# MCU_144_POWER.net
KiCad netlist of a schematic drawn in Altium Designer
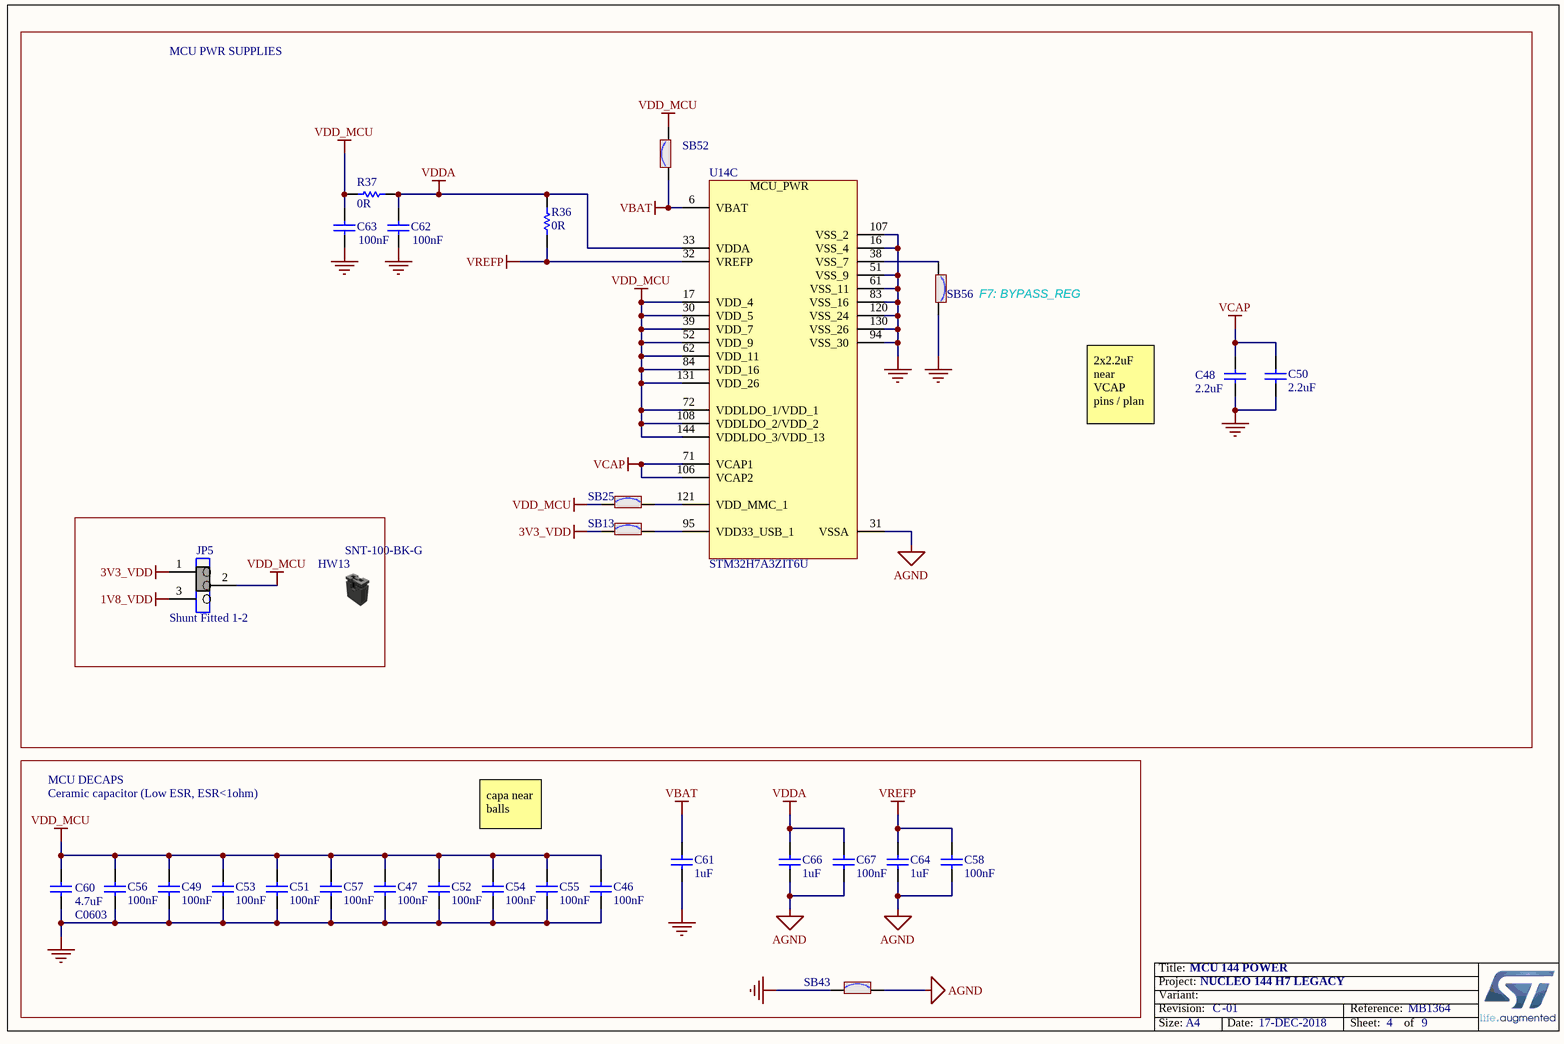
[diagram p0: MCU_144_POWER.SchDoc]

(export (version "E")
  (design (tool "Eeschema 10.0.6"))
  (components
    (comp (ref "C46")
      (value "100nF")
      (footprint "C0402")
      (description "[obsolete] Capacitor, MLCC,100nF, 10V, X7R, 10%, 0402, T=0.5mm")
      (fields
        (field (name "INTERNAL_PART_NUMBER") "MCD-01123")
        (field (name "MANUFACTURER_PART_NUMBER") "NRND_GRM155R71A104KA01")
        (field (name "PROVIDED_BY") "SUBCO")
      )
      (libsource (lib "MCD_PARTS_database") (part "Capacitor"))
    )
    (comp (ref "C47")
      (value "100nF")
      (footprint "C0402")
      (description "[obsolete] Capacitor, MLCC,100nF, 10V, X7R, 10%, 0402, T=0.5mm")
      (fields
        (field (name "INTERNAL_PART_NUMBER") "MCD-01123")
        (field (name "MANUFACTURER_PART_NUMBER") "NRND_GRM155R71A104KA01")
        (field (name "PROVIDED_BY") "SUBCO")
      )
      (libsource (lib "MCD_PARTS_database") (part "Capacitor"))
    )
    (comp (ref "C48")
      (value "2.2uF")
      (footprint "C0603")
      (description "Capacitor, MLCC, 2.2uF, 10V, X5R, 10%, 0603, T=0,8mm")
      (fields
        (field (name "INTERNAL_PART_NUMBER") "MCD-00012")
        (field (name "MANUFACTURER_PART_NUMBER") "CC0603KRX5R6BB225")
        (field (name "PROVIDED_BY") "SUBCO")
      )
      (libsource (lib "MCD_PARTS_database") (part "Capacitor"))
    )
    (comp (ref "C49")
      (value "100nF")
      (footprint "C0402")
      (description "[obsolete] Capacitor, MLCC,100nF, 10V, X7R, 10%, 0402, T=0.5mm")
      (fields
        (field (name "INTERNAL_PART_NUMBER") "MCD-01123")
        (field (name "MANUFACTURER_PART_NUMBER") "NRND_GRM155R71A104KA01")
        (field (name "PROVIDED_BY") "SUBCO")
      )
      (libsource (lib "MCD_PARTS_database") (part "Capacitor"))
    )
    (comp (ref "C50")
      (value "2.2uF")
      (footprint "C0603")
      (description "Capacitor, MLCC, 2.2uF, 10V, X5R, 10%, 0603, T=0,8mm")
      (fields
        (field (name "INTERNAL_PART_NUMBER") "MCD-00012")
        (field (name "MANUFACTURER_PART_NUMBER") "CC0603KRX5R6BB225")
        (field (name "PROVIDED_BY") "SUBCO")
      )
      (libsource (lib "MCD_PARTS_database") (part "Capacitor"))
    )
    (comp (ref "C51")
      (value "100nF")
      (footprint "C0402")
      (description "[obsolete] Capacitor, MLCC,100nF, 10V, X7R, 10%, 0402, T=0.5mm")
      (fields
        (field (name "INTERNAL_PART_NUMBER") "MCD-01123")
        (field (name "MANUFACTURER_PART_NUMBER") "NRND_GRM155R71A104KA01")
        (field (name "PROVIDED_BY") "SUBCO")
      )
      (libsource (lib "MCD_PARTS_database") (part "Capacitor"))
    )
    (comp (ref "C52")
      (value "100nF")
      (footprint "C0402")
      (description "[obsolete] Capacitor, MLCC,100nF, 10V, X7R, 10%, 0402, T=0.5mm")
      (fields
        (field (name "INTERNAL_PART_NUMBER") "MCD-01123")
        (field (name "MANUFACTURER_PART_NUMBER") "NRND_GRM155R71A104KA01")
        (field (name "PROVIDED_BY") "SUBCO")
      )
      (libsource (lib "MCD_PARTS_database") (part "Capacitor"))
    )
    (comp (ref "C53")
      (value "100nF")
      (footprint "C0402")
      (description "[obsolete] Capacitor, MLCC,100nF, 10V, X7R, 10%, 0402, T=0.5mm")
      (fields
        (field (name "INTERNAL_PART_NUMBER") "MCD-01123")
        (field (name "MANUFACTURER_PART_NUMBER") "NRND_GRM155R71A104KA01")
        (field (name "PROVIDED_BY") "SUBCO")
      )
      (libsource (lib "MCD_PARTS_database") (part "Capacitor"))
    )
    (comp (ref "C54")
      (value "100nF")
      (footprint "C0402")
      (description "[obsolete] Capacitor, MLCC,100nF, 10V, X7R, 10%, 0402, T=0.5mm")
      (fields
        (field (name "INTERNAL_PART_NUMBER") "MCD-01123")
        (field (name "MANUFACTURER_PART_NUMBER") "NRND_GRM155R71A104KA01")
        (field (name "PROVIDED_BY") "SUBCO")
      )
      (libsource (lib "MCD_PARTS_database") (part "Capacitor"))
    )
    (comp (ref "C55")
      (value "100nF")
      (footprint "C0402")
      (description "[obsolete] Capacitor, MLCC,100nF, 10V, X7R, 10%, 0402, T=0.5mm")
      (fields
        (field (name "INTERNAL_PART_NUMBER") "MCD-01123")
        (field (name "MANUFACTURER_PART_NUMBER") "NRND_GRM155R71A104KA01")
        (field (name "PROVIDED_BY") "SUBCO")
      )
      (libsource (lib "MCD_PARTS_database") (part "Capacitor"))
    )
    (comp (ref "C56")
      (value "100nF")
      (footprint "C0402")
      (description "[obsolete] Capacitor, MLCC,100nF, 10V, X7R, 10%, 0402, T=0.5mm")
      (fields
        (field (name "INTERNAL_PART_NUMBER") "MCD-01123")
        (field (name "MANUFACTURER_PART_NUMBER") "NRND_GRM155R71A104KA01")
        (field (name "PROVIDED_BY") "SUBCO")
      )
      (libsource (lib "MCD_PARTS_database") (part "Capacitor"))
    )
    (comp (ref "C57")
      (value "100nF")
      (footprint "C0402")
      (description "[obsolete] Capacitor, MLCC,100nF, 10V, X7R, 10%, 0402, T=0.5mm")
      (fields
        (field (name "INTERNAL_PART_NUMBER") "MCD-01123")
        (field (name "MANUFACTURER_PART_NUMBER") "NRND_GRM155R71A104KA01")
        (field (name "PROVIDED_BY") "SUBCO")
      )
      (libsource (lib "MCD_PARTS_database") (part "Capacitor"))
    )
    (comp (ref "C58")
      (value "100nF")
      (footprint "C0402")
      (description "[obsolete] Capacitor, MLCC,100nF, 10V, X7R, 10%, 0402, T=0.5mm")
      (fields
        (field (name "INTERNAL_PART_NUMBER") "MCD-01123")
        (field (name "MANUFACTURER_PART_NUMBER") "NRND_GRM155R71A104KA01")
        (field (name "PROVIDED_BY") "SUBCO")
      )
      (libsource (lib "MCD_PARTS_database") (part "Capacitor"))
    )
    (comp (ref "C60")
      (value "4.7uF")
      (footprint "C0603")
      (description "Capacitor, MLCC, 4.7µF, 10V, X5R, 20%, 0603, T=0,8mm")
      (fields
        (field (name "INTERNAL_PART_NUMBER") "MCD-01121")
        (field (name "MANUFACTURER_PART_NUMBER") "GRM188R61A475ME15")
        (field (name "PACKAGE") "C0603")
        (field (name "PROVIDED_BY") "SUBCO")
      )
      (libsource (lib "MCD_PARTS_database") (part "Capacitor"))
    )
    (comp (ref "C61")
      (value "1uF")
      (footprint "C0603")
      (description "Capacitor, MLCC, 1uF, 6V3, X5R, 10%, 0603, T=0,8mm")
      (fields
        (field (name "INTERNAL_PART_NUMBER") "MCD-00238")
        (field (name "MANUFACTURER_PART_NUMBER") "CC0603KRX5R5BB105")
        (field (name "PROVIDED_BY") "SUBCO")
      )
      (libsource (lib "MCD_PARTS_database") (part "Capacitor"))
    )
    (comp (ref "C62")
      (value "100nF")
      (footprint "C0402")
      (description "Capacitor, MLCC, 100nF, 16V, X7R, 10%, 0402, T=0.5mm")
      (fields
        (field (name "INTERNAL_PART_NUMBER") "MCD-00006")
        (field (name "MANUFACTURER_PART_NUMBER") "CC0402KRX7R7BB104")
        (field (name "PROVIDED_BY") "SUBCO")
      )
      (libsource (lib "MCD_PARTS_database") (part "Capacitor"))
    )
    (comp (ref "C63")
      (value "100nF")
      (footprint "C0402")
      (description "Capacitor, MLCC, 100nF, 16V, X7R, 10%, 0402, T=0.5mm")
      (fields
        (field (name "INTERNAL_PART_NUMBER") "MCD-00006")
        (field (name "MANUFACTURER_PART_NUMBER") "CC0402KRX7R7BB104")
        (field (name "PROVIDED_BY") "SUBCO")
      )
      (libsource (lib "MCD_PARTS_database") (part "Capacitor"))
    )
    (comp (ref "C64")
      (value "1uF")
      (footprint "C0603")
      (description "Capacitor, MLCC, 1uF, 6V3, X5R, 10%, 0603, T=0,8mm")
      (fields
        (field (name "INTERNAL_PART_NUMBER") "MCD-00238")
        (field (name "MANUFACTURER_PART_NUMBER") "CC0603KRX5R5BB105")
        (field (name "PROVIDED_BY") "SUBCO")
      )
      (libsource (lib "MCD_PARTS_database") (part "Capacitor"))
    )
    (comp (ref "C66")
      (value "1uF")
      (footprint "C0603")
      (description "Capacitor, MLCC, 1uF, 6V3, X5R, 10%, 0603, T=0,8mm")
      (fields
        (field (name "INTERNAL_PART_NUMBER") "MCD-00238")
        (field (name "MANUFACTURER_PART_NUMBER") "CC0603KRX5R5BB105")
        (field (name "PROVIDED_BY") "SUBCO")
      )
      (libsource (lib "MCD_PARTS_database") (part "Capacitor"))
    )
    (comp (ref "C67")
      (value "100nF")
      (footprint "C0402")
      (description "[obsolete] Capacitor, MLCC,100nF, 10V, X7R, 10%, 0402, T=0.5mm")
      (fields
        (field (name "INTERNAL_PART_NUMBER") "MCD-01123")
        (field (name "MANUFACTURER_PART_NUMBER") "NRND_GRM155R71A104KA01")
        (field (name "PROVIDED_BY") "SUBCO")
      )
      (libsource (lib "MCD_PARTS_database") (part "Capacitor"))
    )
    (comp (ref "HW13")
      (value "SNT-100-BK-G")
      (description "SHUNT 2.54mm BLACK")
      (fields
        (field (name "INTERNAL_PART_NUMBER") "MCD-00043")
        (field (name "MANUFACTURER") "SAMTEC")
        (field (name "PROVIDED_BY") "SUBCO")
      )
      (libsource (lib "MCD_PARTS_database") (part "Shunt Black 2.54mm"))
    )
    (comp (ref "JP5")
      (value "Shunt Fitted 1-2")
      (footprint "CON_SAMTEC_TSW-103-07-F-S")
      (description "Header, 3x1, 2,54mm, VR, TH, Height 5.84mm/2.54mm - Shunt Fitted 1-2 by default")
      (fields
        (field (name "INTERNAL_PART_NUMBER") "MCD-00684")
        (field (name "MANUFACTURER_PART_NUMBER") "TSW-103-07-F-S")
        (field (name "PROVIDED_BY") "SUBCO")
      )
      (libsource (lib "MCD_PARTS_database") (part "Jumper_Header 3x1 Fitted 1-2"))
    )
    (comp (ref "R36")
      (value "0R")
      (footprint "R0603")
      (description "Resistor,0R,0603,5%,1/10W")
      (fields
        (field (name "INTERNAL_PART_NUMBER") "MCD-00056")
        (field (name "MANUFACTURER_PART_NUMBER") "RC0603JR-070RL")
        (field (name "PROVIDED_BY") "SUBCO")
      )
      (libsource (lib "MCD_PARTS_database") (part "Resistor"))
    )
    (comp (ref "R37")
      (value "0R")
      (footprint "R0603")
      (description "Resistor,0R,0603,5%,1/10W")
      (fields
        (field (name "INTERNAL_PART_NUMBER") "MCD-00056")
        (field (name "MANUFACTURER_PART_NUMBER") "RC0603JR-070RL")
        (field (name "PROVIDED_BY") "SUBCO")
      )
      (libsource (lib "MCD_PARTS_database") (part "Resistor"))
    )
    (comp (ref "SB13")
      (value "SB_ON")
      (footprint "SOLDER-BRIDGE_R0603-0R")
      (description "Solder Bridge ON")
      (fields
        (field (name "INTERNAL_PART_NUMBER") "MCD-00071")
        (field (name "MANUFACTURER_PART_NUMBER") "RC0603JR-070RL")
        (field (name "PROVIDED_BY") "SUBCO")
      )
      (libsource (lib "MCD_PARTS_database") (part "SB_ON"))
    )
    (comp (ref "SB25")
      (value "SB_ON")
      (footprint "SOLDER-BRIDGE_R0603-0R")
      (description "Solder Bridge ON")
      (fields
        (field (name "INTERNAL_PART_NUMBER") "MCD-00071")
        (field (name "MANUFACTURER_PART_NUMBER") "RC0603JR-070RL")
        (field (name "PROVIDED_BY") "SUBCO")
      )
      (libsource (lib "MCD_PARTS_database") (part "SB_ON"))
    )
    (comp (ref "SB43")
      (value "SB_ON")
      (footprint "SOLDER-BRIDGE_R0603-0R")
      (description "Solder Bridge ON")
      (fields
        (field (name "INTERNAL_PART_NUMBER") "MCD-00071")
        (field (name "MANUFACTURER_PART_NUMBER") "RC0603JR-070RL")
        (field (name "PROVIDED_BY") "SUBCO")
      )
      (libsource (lib "MCD_PARTS_database") (part "SB_ON"))
    )
    (comp (ref "SB52")
      (value "SB_ON")
      (footprint "SOLDER-BRIDGE_R0603-0R")
      (description "Solder Bridge ON")
      (fields
        (field (name "INTERNAL_PART_NUMBER") "MCD-00071")
        (field (name "MANUFACTURER_PART_NUMBER") "RC0603JR-070RL")
        (field (name "PROVIDED_BY") "SUBCO")
      )
      (libsource (lib "") (part "SB_ON_2"))
    )
    (comp (ref "SB56")
      (value "SB_ON")
      (footprint "SOLDER-BRIDGE_R0603-0R")
      (description "Solder Bridge ON")
      (fields
        (field (name "INTERNAL_PART_NUMBER") "MCD-00071")
        (field (name "MANUFACTURER_PART_NUMBER") "RC0603JR-070RL")
        (field (name "PROVIDED_BY") "SUBCO")
      )
      (libsource (lib "") (part "SB_ON_1"))
    )
    (comp (ref "U14")
      (value "STM32H7A3ZIT6U")
      (footprint "ICC_LQFP144_20X20_P050_SOCKET_YAMAICHI_IC149-144-145-B5_NM")
      (description "STM32H7A3ZIT6U, LQFP144 package, 20x20")
      (fields
        (field (name "INTERNAL_PART_NUMBER") "MCD-01349")
        (field (name "MANUFACTURER") "STMICROELECTRONICS")
        (field (name "PROVIDED_BY") "SUBCO with ST control")
      )
      (libsource (lib "MCD_PARTS_database") (part "STM32H7A3ZIT6"))
    )
  )
  (nets
    (net (code "1") (name "1V8_VDD") (class "Default")
      (node (ref "JP5") (pin "3") (pinfunction "3_3") (pintype "passive"))
    )
    (net (code "2") (name "3V3_VDD") (class "Default")
      (node (ref "JP5") (pin "1") (pinfunction "1_1") (pintype "passive"))
      (node (ref "SB13") (pin "1") (pinfunction "1_1") (pintype "passive"))
    )
    (net (code "3") (name "AGND") (class "Default")
      (node (ref "C58") (pin "1") (pinfunction "1_1") (pintype "passive"))
      (node (ref "C64") (pin "2") (pinfunction "2_2") (pintype "passive"))
      (node (ref "C66") (pin "2") (pinfunction "2_2") (pintype "passive"))
      (node (ref "C67") (pin "1") (pinfunction "1_1") (pintype "passive"))
      (node (ref "SB43") (pin "2") (pinfunction "2_2") (pintype "passive"))
      (node (ref "U14") (pin "31") (pinfunction "VSSA_31") (pintype "passive"))
    )
    (net (code "4") (name "GND") (class "Default")
      (node (ref "C46") (pin "1") (pinfunction "1_1") (pintype "passive"))
      (node (ref "C47") (pin "1") (pinfunction "1_1") (pintype "passive"))
      (node (ref "C48") (pin "1") (pinfunction "1_1") (pintype "passive"))
      (node (ref "C49") (pin "1") (pinfunction "1_1") (pintype "passive"))
      (node (ref "C50") (pin "1") (pinfunction "1_1") (pintype "passive"))
      (node (ref "C51") (pin "1") (pinfunction "1_1") (pintype "passive"))
      (node (ref "C52") (pin "1") (pinfunction "1_1") (pintype "passive"))
      (node (ref "C53") (pin "1") (pinfunction "1_1") (pintype "passive"))
      (node (ref "C54") (pin "1") (pinfunction "1_1") (pintype "passive"))
      (node (ref "C55") (pin "1") (pinfunction "1_1") (pintype "passive"))
      (node (ref "C56") (pin "1") (pinfunction "1_1") (pintype "passive"))
      (node (ref "C57") (pin "1") (pinfunction "1_1") (pintype "passive"))
      (node (ref "C60") (pin "1") (pinfunction "1_1") (pintype "passive"))
      (node (ref "C61") (pin "1") (pinfunction "1_1") (pintype "passive"))
      (node (ref "C62") (pin "2") (pinfunction "2_2") (pintype "passive"))
      (node (ref "C63") (pin "2") (pinfunction "2_2") (pintype "passive"))
      (node (ref "SB43") (pin "1") (pinfunction "1_1") (pintype "passive"))
      (node (ref "SB56") (pin "2") (pinfunction "2_2") (pintype "passive"))
      (node (ref "U14") (pin "107") (pinfunction "VSS_2_107") (pintype "passive"))
      (node (ref "U14") (pin "120") (pinfunction "VSS_24_120") (pintype "passive"))
      (node (ref "U14") (pin "130") (pinfunction "VSS_26_130") (pintype "passive"))
      (node (ref "U14") (pin "16") (pinfunction "VSS_4_16") (pintype "passive"))
      (node (ref "U14") (pin "51") (pinfunction "VSS_9_51") (pintype "passive"))
      (node (ref "U14") (pin "61") (pinfunction "VSS_11_61") (pintype "passive"))
      (node (ref "U14") (pin "83") (pinfunction "VSS_16_83") (pintype "passive"))
      (node (ref "U14") (pin "94") (pinfunction "VSS_30_94") (pintype "passive"))
    )
    (net (code "5") (name "Net-(U14C-VDD33_USB_1)") (class "Default")
      (node (ref "SB13") (pin "2") (pinfunction "2_2") (pintype "passive"))
      (node (ref "U14") (pin "95") (pinfunction "VDD33_USB_1_95") (pintype "passive"))
    )
    (net (code "6") (name "Net-(U14C-VDD_MMC_1)") (class "Default")
      (node (ref "SB25") (pin "2") (pinfunction "2_2") (pintype "passive"))
      (node (ref "U14") (pin "121") (pinfunction "VDD_MMC_1_121") (pintype "passive"))
    )
    (net (code "7") (name "Net-(U14C-VSS_7)") (class "Default")
      (node (ref "SB56") (pin "1") (pinfunction "1_1") (pintype "passive"))
      (node (ref "U14") (pin "38") (pinfunction "VSS_7_38") (pintype "passive"))
    )
    (net (code "8") (name "VBAT") (class "Default")
      (node (ref "C61") (pin "2") (pinfunction "2_2") (pintype "passive"))
      (node (ref "SB52") (pin "1") (pinfunction "1_1") (pintype "passive"))
      (node (ref "U14") (pin "6") (pinfunction "VBAT_6") (pintype "passive"))
    )
    (net (code "9") (name "VCAP") (class "Default")
      (node (ref "C48") (pin "2") (pinfunction "2_2") (pintype "passive"))
      (node (ref "C50") (pin "2") (pinfunction "2_2") (pintype "passive"))
      (node (ref "U14") (pin "106") (pinfunction "VCAP2_106") (pintype "passive"))
      (node (ref "U14") (pin "71") (pinfunction "VCAP1_71") (pintype "passive"))
    )
    (net (code "10") (name "VDDA") (class "Default")
      (node (ref "C62") (pin "1") (pinfunction "1_1") (pintype "passive"))
      (node (ref "C66") (pin "1") (pinfunction "1_1") (pintype "passive"))
      (node (ref "C67") (pin "2") (pinfunction "2_2") (pintype "passive"))
      (node (ref "R36") (pin "1") (pinfunction "1_1") (pintype "passive"))
      (node (ref "R37") (pin "2") (pinfunction "2_2") (pintype "passive"))
      (node (ref "U14") (pin "33") (pinfunction "VDDA_33") (pintype "passive"))
    )
    (net (code "11") (name "VDD_MCU") (class "Default")
      (node (ref "C46") (pin "2") (pinfunction "2_2") (pintype "passive"))
      (node (ref "C47") (pin "2") (pinfunction "2_2") (pintype "passive"))
      (node (ref "C49") (pin "2") (pinfunction "2_2") (pintype "passive"))
      (node (ref "C51") (pin "2") (pinfunction "2_2") (pintype "passive"))
      (node (ref "C52") (pin "2") (pinfunction "2_2") (pintype "passive"))
      (node (ref "C53") (pin "2") (pinfunction "2_2") (pintype "passive"))
      (node (ref "C54") (pin "2") (pinfunction "2_2") (pintype "passive"))
      (node (ref "C55") (pin "2") (pinfunction "2_2") (pintype "passive"))
      (node (ref "C56") (pin "2") (pinfunction "2_2") (pintype "passive"))
      (node (ref "C57") (pin "2") (pinfunction "2_2") (pintype "passive"))
      (node (ref "C60") (pin "2") (pinfunction "2_2") (pintype "passive"))
      (node (ref "C63") (pin "1") (pinfunction "1_1") (pintype "passive"))
      (node (ref "JP5") (pin "2") (pinfunction "2_2") (pintype "passive"))
      (node (ref "R37") (pin "1") (pinfunction "1_1") (pintype "passive"))
      (node (ref "SB25") (pin "1") (pinfunction "1_1") (pintype "passive"))
      (node (ref "SB52") (pin "2") (pinfunction "2_2") (pintype "passive"))
      (node (ref "U14") (pin "108") (pinfunction "VDDLDO_2/VDD_2_108") (pintype "passive"))
      (node (ref "U14") (pin "131") (pinfunction "VDD_26_131") (pintype "passive"))
      (node (ref "U14") (pin "144") (pinfunction "VDDLDO_3/VDD_13_144") (pintype "passive"))
      (node (ref "U14") (pin "17") (pinfunction "VDD_4_17") (pintype "passive"))
      (node (ref "U14") (pin "30") (pinfunction "VDD_5_30") (pintype "passive"))
      (node (ref "U14") (pin "39") (pinfunction "VDD_7_39") (pintype "passive"))
      (node (ref "U14") (pin "52") (pinfunction "VDD_9_52") (pintype "passive"))
      (node (ref "U14") (pin "62") (pinfunction "VDD_11_62") (pintype "passive"))
      (node (ref "U14") (pin "72") (pinfunction "VDDLDO_1/VDD_1_72") (pintype "passive"))
      (node (ref "U14") (pin "84") (pinfunction "VDD_16_84") (pintype "passive"))
    )
    (net (code "12") (name "VREFP") (class "Default")
      (node (ref "C58") (pin "2") (pinfunction "2_2") (pintype "passive"))
      (node (ref "C64") (pin "1") (pinfunction "1_1") (pintype "passive"))
      (node (ref "R36") (pin "2") (pinfunction "2_2") (pintype "passive"))
      (node (ref "U14") (pin "32") (pinfunction "VREFP_32") (pintype "passive"))
    )
  )
)
